# working.net
KiCad netlist of a schematic drawn in EAGLE
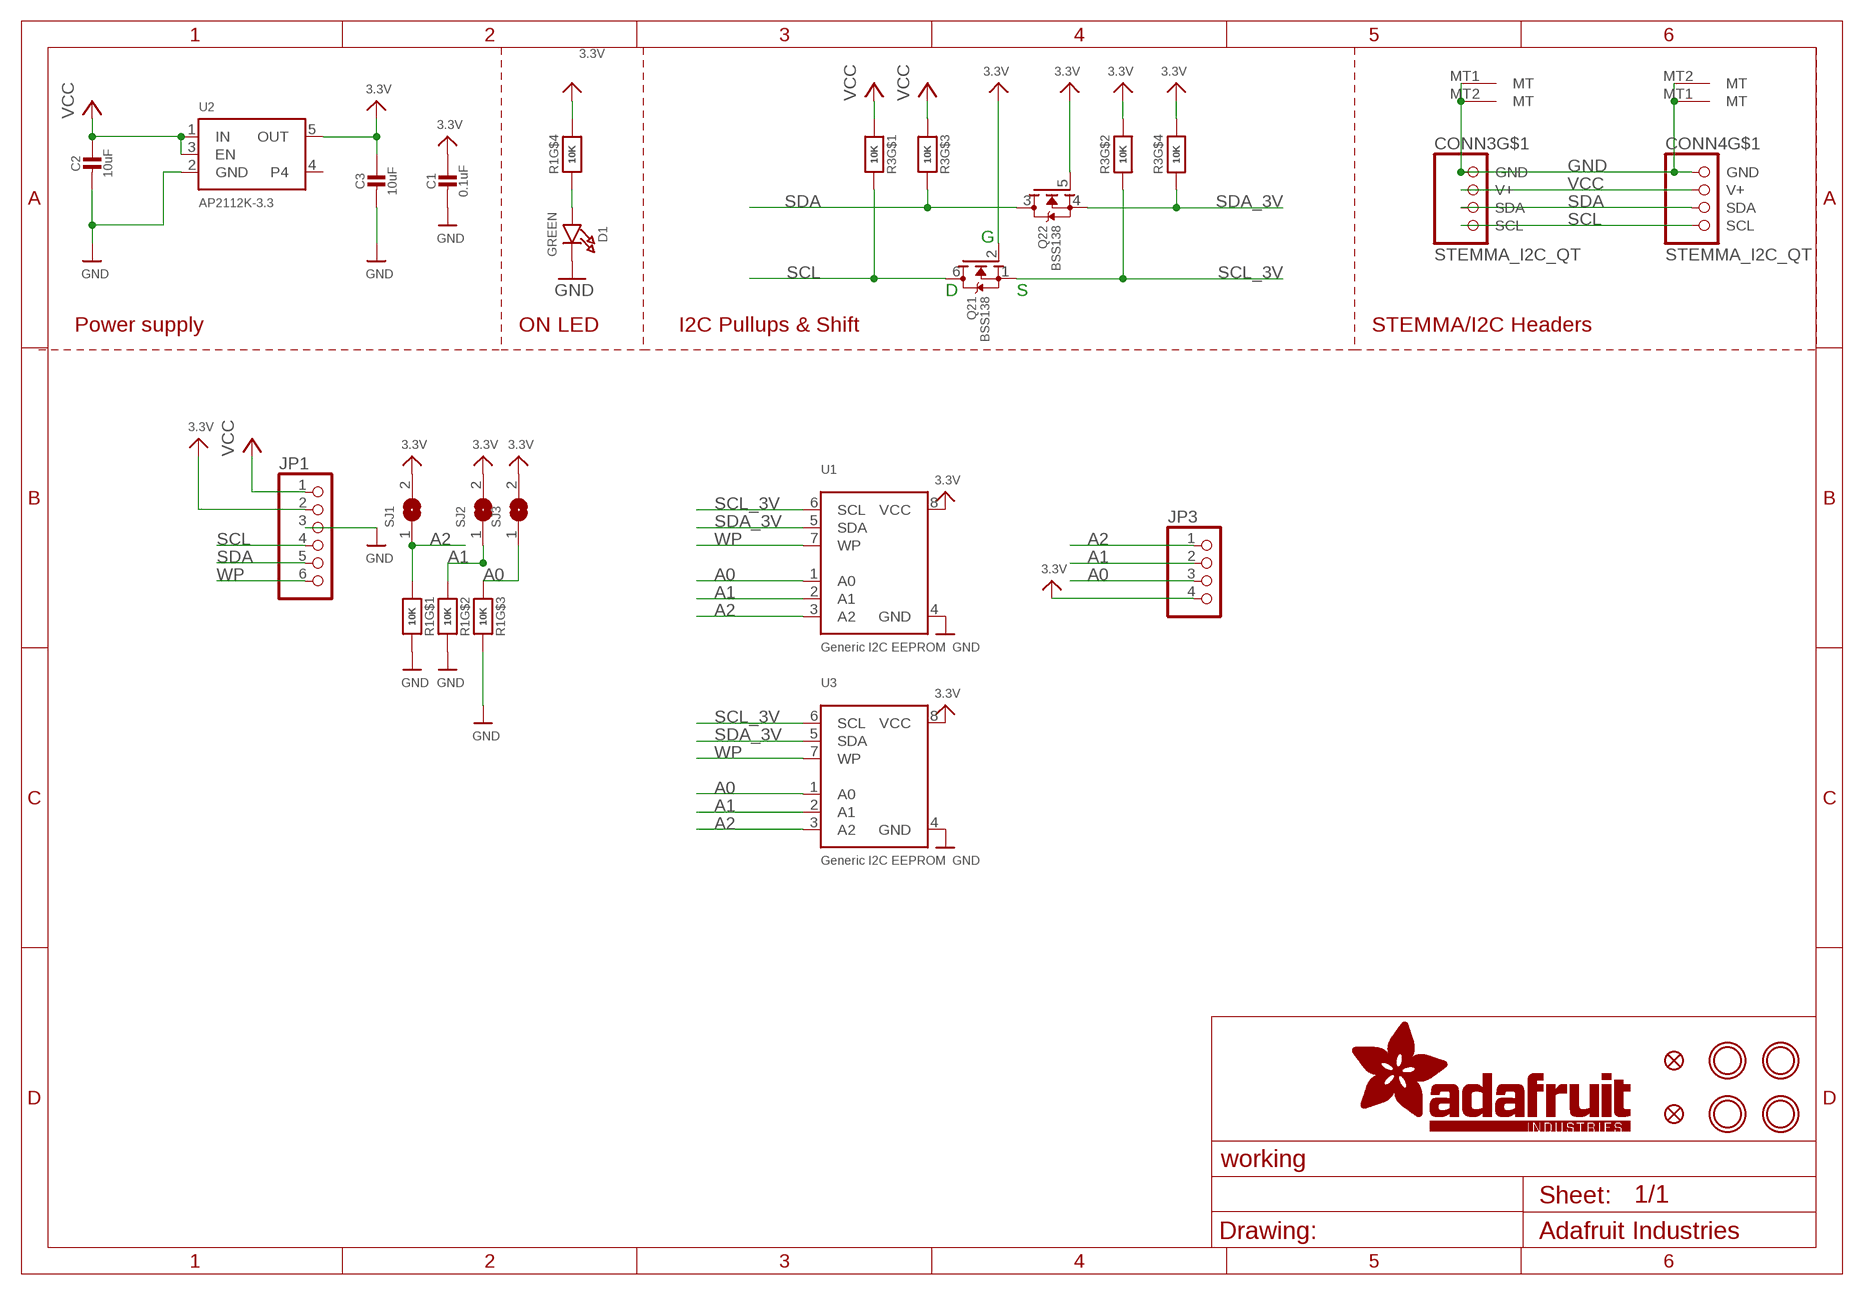
[diagram p0: schematic, sheet 1]

(export (version "E")
  (design (tool "Eeschema 10.0.6"))
  (components
    (comp (ref "C1")
      (value "0.1uF")
      (footprint "eagle-import:0603-NO")
      (libsource (lib "eagle-import") (part "CAP_CERAMIC0603_NO"))
    )
    (comp (ref "C2")
      (value "10uF")
      (footprint "eagle-import:0805-NO")
      (libsource (lib "eagle-import") (part "CAP_CERAMIC0805-NOOUTLINE"))
    )
    (comp (ref "C3")
      (value "10uF")
      (footprint "eagle-import:0805-NO")
      (libsource (lib "eagle-import") (part "CAP_CERAMIC0805-NOOUTLINE"))
    )
    (comp (ref "CONN3")
      (value "STEMMA_I2C_QT")
      (footprint "eagle-import:JST_SH4")
      (libsource (lib "eagle-import") (part "STEMMA_I2C_QT"))
    )
    (comp (ref "CONN4")
      (value "STEMMA_I2C_QT")
      (footprint "eagle-import:JST_SH4")
      (libsource (lib "eagle-import") (part "STEMMA_I2C_QT"))
    )
    (comp (ref "D1")
      (value "GREEN")
      (footprint "eagle-import:CHIPLED_0603_NOOUTLINE")
      (libsource (lib "eagle-import") (part "LED0603_NOOUTLINE"))
    )
    (comp (ref "FID3")
      (value "FIDUCIAL_1MM")
      (footprint "eagle-import:FIDUCIAL_1MM")
      (libsource (lib "eagle-import") (part "FIDUCIAL_1MM"))
    )
    (comp (ref "FID4")
      (value "FIDUCIAL_1MM")
      (footprint "eagle-import:FIDUCIAL_1MM")
      (libsource (lib "eagle-import") (part "FIDUCIAL_1MM"))
    )
    (comp (ref "JP1")
      (value "HEADER-1X670MIL")
      (footprint "eagle-import:1X06_ROUND_70")
      (libsource (lib "eagle-import") (part "HEADER-1X670MIL"))
    )
    (comp (ref "JP3")
      (value "HEADER-1X4ROUND")
      (footprint "eagle-import:1X04_ROUND")
      (libsource (lib "eagle-import") (part "HEADER-1X4ROUND"))
    )
    (comp (ref "Q2")
      (value "BSS138")
      (footprint "eagle-import:SOT363")
      (libsource (lib "eagle-import") (part "MOSFET-N_DUAL"))
    )
    (comp (ref "R1")
      (value "10K")
      (footprint "eagle-import:RESPACK_4X0603")
      (libsource (lib "eagle-import") (part "RESISTOR_4PACK"))
    )
    (comp (ref "R3")
      (value "10K")
      (footprint "eagle-import:RESPACK_4X0603")
      (libsource (lib "eagle-import") (part "RESISTOR_4PACK"))
    )
    (comp (ref "SJ1")
      (value "SOLDERJUMPER")
      (footprint "eagle-import:SOLDERJUMPER_ARROW_NOPASTE")
      (libsource (lib "eagle-import") (part "SOLDERJUMPER"))
    )
    (comp (ref "SJ2")
      (value "SOLDERJUMPER")
      (footprint "eagle-import:SOLDERJUMPER_ARROW_NOPASTE")
      (libsource (lib "eagle-import") (part "SOLDERJUMPER"))
    )
    (comp (ref "SJ3")
      (value "SOLDERJUMPER")
      (footprint "eagle-import:SOLDERJUMPER_ARROW_NOPASTE")
      (libsource (lib "eagle-import") (part "SOLDERJUMPER"))
    )
    (comp (ref "U$1")
      (value "MOUNTINGHOLE2.5")
      (footprint "eagle-import:MOUNTINGHOLE_2.5_PLATED")
      (libsource (lib "eagle-import") (part "MOUNTINGHOLE2.5"))
    )
    (comp (ref "U$17")
      (value "MOUNTINGHOLE2.5")
      (footprint "eagle-import:MOUNTINGHOLE_2.5_PLATED")
      (libsource (lib "eagle-import") (part "MOUNTINGHOLE2.5"))
    )
    (comp (ref "U$19")
      (value "MOUNTINGHOLE2.5")
      (footprint "eagle-import:MOUNTINGHOLE_2.5_PLATED")
      (libsource (lib "eagle-import") (part "MOUNTINGHOLE2.5"))
    )
    (comp (ref "U$21")
      (value "MOUNTINGHOLE2.5")
      (footprint "eagle-import:MOUNTINGHOLE_2.5_PLATED")
      (libsource (lib "eagle-import") (part "MOUNTINGHOLE2.5"))
    )
    (comp (ref "U1")
      (value "Generic I2C EEPROM")
      (footprint "eagle-import:SOIC8_150MIL")
      (libsource (lib "eagle-import") (part "EEPROM_I2C_8PIN_GENERIC"))
    )
    (comp (ref "U2")
      (value "AP2112K-3.3")
      (footprint "eagle-import:SOT23-5")
      (libsource (lib "eagle-import") (part "VREG_SOT23-5"))
    )
    (comp (ref "U3")
      (value "Generic I2C EEPROM")
      (footprint "eagle-import:USON8")
      (libsource (lib "eagle-import") (part "EEPROM_I2C_8PIN_GENERIC_SON8"))
    )
  )
  (nets
    (net (code "1") (name "/A0") (class "Default")
      (node (ref "JP3") (pin "3") (pinfunction "3_3") (pintype "passive"))
      (node (ref "R1") (pin "3") (pinfunction "1_3") (pintype "passive"))
      (node (ref "SJ3") (pin "1") (pinfunction "1_1") (pintype "passive"))
      (node (ref "U1") (pin "1") (pinfunction "A0_1") (pintype "input"))
      (node (ref "U3") (pin "1") (pinfunction "A0_1") (pintype "input"))
    )
    (net (code "2") (name "/A1") (class "Default")
      (node (ref "JP3") (pin "2") (pinfunction "2_2") (pintype "passive"))
      (node (ref "R1") (pin "2") (pinfunction "1_2") (pintype "passive"))
      (node (ref "SJ2") (pin "1") (pinfunction "1_1") (pintype "passive"))
      (node (ref "U1") (pin "2") (pinfunction "A1_2") (pintype "input"))
      (node (ref "U3") (pin "2") (pinfunction "A1_2") (pintype "input"))
    )
    (net (code "3") (name "/A2") (class "Default")
      (node (ref "JP3") (pin "1") (pinfunction "1_1") (pintype "passive"))
      (node (ref "R1") (pin "1") (pinfunction "1_1") (pintype "passive"))
      (node (ref "SJ1") (pin "1") (pinfunction "1_1") (pintype "passive"))
      (node (ref "U1") (pin "3") (pinfunction "A2_3") (pintype "input"))
      (node (ref "U3") (pin "3") (pinfunction "A2_3") (pintype "input"))
    )
    (net (code "4") (name "/SCL") (class "Default")
      (node (ref "CONN3") (pin "4") (pinfunction "SCL_4") (pintype "passive"))
      (node (ref "CONN4") (pin "4") (pinfunction "SCL_4") (pintype "passive"))
      (node (ref "JP1") (pin "4") (pinfunction "4_4") (pintype "passive"))
      (node (ref "Q2") (pin "6") (pinfunction "D_6") (pintype "bidirectional"))
      (node (ref "R3") (pin "8") (pinfunction "2_8") (pintype "passive"))
    )
    (net (code "5") (name "/SCL_3V") (class "Default")
      (node (ref "Q2") (pin "1") (pinfunction "S_1") (pintype "bidirectional"))
      (node (ref "R3") (pin "7") (pinfunction "2_7") (pintype "passive"))
      (node (ref "U1") (pin "6") (pinfunction "SCL_6") (pintype "input"))
      (node (ref "U3") (pin "6") (pinfunction "SCL_6") (pintype "input"))
    )
    (net (code "6") (name "/SDA") (class "Default")
      (node (ref "CONN3") (pin "3") (pinfunction "SDA_3") (pintype "passive"))
      (node (ref "CONN4") (pin "3") (pinfunction "SDA_3") (pintype "passive"))
      (node (ref "JP1") (pin "5") (pinfunction "5_5") (pintype "passive"))
      (node (ref "Q2") (pin "3") (pinfunction "D_3") (pintype "bidirectional"))
      (node (ref "R3") (pin "6") (pinfunction "2_6") (pintype "passive"))
    )
    (net (code "7") (name "/SDA_3V") (class "Default")
      (node (ref "Q2") (pin "4") (pinfunction "S_4") (pintype "bidirectional"))
      (node (ref "R3") (pin "5") (pinfunction "2_5") (pintype "passive"))
      (node (ref "U1") (pin "5") (pinfunction "SDA_5") (pintype "bidirectional"))
      (node (ref "U3") (pin "5") (pinfunction "SDA_5") (pintype "bidirectional"))
    )
    (net (code "8") (name "/WP") (class "Default")
      (node (ref "JP1") (pin "6") (pinfunction "6_6") (pintype "passive"))
      (node (ref "U1") (pin "7") (pinfunction "WP_7") (pintype "input"))
      (node (ref "U3") (pin "7") (pinfunction "WP_7") (pintype "input"))
    )
    (net (code "9") (name "3.3V") (class "Default")
      (node (ref "C1") (pin "1") (pinfunction "1_1") (pintype "passive"))
      (node (ref "C3") (pin "1") (pinfunction "1_1") (pintype "passive"))
      (node (ref "JP1") (pin "2") (pinfunction "2_2") (pintype "passive"))
      (node (ref "JP3") (pin "4") (pinfunction "4_4") (pintype "passive"))
      (node (ref "Q2") (pin "2") (pinfunction "G_2") (pintype "bidirectional"))
      (node (ref "Q2") (pin "5") (pinfunction "G_5") (pintype "bidirectional"))
      (node (ref "R1") (pin "5") (pinfunction "2_5") (pintype "passive"))
      (node (ref "R3") (pin "2") (pinfunction "1_2") (pintype "passive"))
      (node (ref "R3") (pin "4") (pinfunction "1_4") (pintype "passive"))
      (node (ref "SJ1") (pin "2") (pinfunction "2_2") (pintype "passive"))
      (node (ref "SJ2") (pin "2") (pinfunction "2_2") (pintype "passive"))
      (node (ref "SJ3") (pin "2") (pinfunction "2_2") (pintype "passive"))
      (node (ref "U1") (pin "8") (pinfunction "VCC_8") (pintype "power_in"))
      (node (ref "U2") (pin "5") (pinfunction "OUT_5") (pintype "power_in"))
      (node (ref "U3") (pin "8") (pinfunction "VCC_8") (pintype "power_in"))
    )
    (net (code "10") (name "GND") (class "Default")
      (node (ref "C1") (pin "2") (pinfunction "2_2") (pintype "passive"))
      (node (ref "C2") (pin "2") (pinfunction "2_2") (pintype "passive"))
      (node (ref "C3") (pin "2") (pinfunction "2_2") (pintype "passive"))
      (node (ref "CONN3") (pin "1") (pinfunction "GND_1") (pintype "passive"))
      (node (ref "CONN3") (pin "MT1") (pinfunction "MT_MT1") (pintype "bidirectional"))
      (node (ref "CONN3") (pin "MT2") (pinfunction "MT_MT2") (pintype "bidirectional"))
      (node (ref "CONN4") (pin "1") (pinfunction "GND_1") (pintype "passive"))
      (node (ref "CONN4") (pin "MT1") (pinfunction "MT_MT1") (pintype "bidirectional"))
      (node (ref "CONN4") (pin "MT2") (pinfunction "MT_MT2") (pintype "bidirectional"))
      (node (ref "D1") (pin "C") (pinfunction "C_C") (pintype "passive"))
      (node (ref "JP1") (pin "3") (pinfunction "3_3") (pintype "passive"))
      (node (ref "R1") (pin "6") (pinfunction "2_6") (pintype "passive"))
      (node (ref "R1") (pin "7") (pinfunction "2_7") (pintype "passive"))
      (node (ref "R1") (pin "8") (pinfunction "2_8") (pintype "passive"))
      (node (ref "U1") (pin "4") (pinfunction "GND_4") (pintype "power_in"))
      (node (ref "U2") (pin "2") (pinfunction "GND_2") (pintype "power_in"))
      (node (ref "U3") (pin "4") (pinfunction "GND_4") (pintype "power_in"))
    )
    (net (code "11") (name "Net-(R1D-1)") (class "Default")
      (node (ref "D1") (pin "A") (pinfunction "A_A") (pintype "passive"))
      (node (ref "R1") (pin "4") (pinfunction "1_4") (pintype "passive"))
    )
    (net (code "12") (name "VCC") (class "Default")
      (node (ref "C2") (pin "1") (pinfunction "1_1") (pintype "passive"))
      (node (ref "CONN3") (pin "2") (pinfunction "V+_2") (pintype "passive"))
      (node (ref "CONN4") (pin "2") (pinfunction "V+_2") (pintype "passive"))
      (node (ref "JP1") (pin "1") (pinfunction "1_1") (pintype "passive"))
      (node (ref "R3") (pin "1") (pinfunction "1_1") (pintype "passive"))
      (node (ref "R3") (pin "3") (pinfunction "1_3") (pintype "passive"))
      (node (ref "U2") (pin "1") (pinfunction "IN_1") (pintype "power_in"))
      (node (ref "U2") (pin "3") (pinfunction "EN_3") (pintype "input"))
    )
    (net (code "13") (name "unconnected-(U2-P4-Pad4)") (class "Default")
      (node (ref "U2") (pin "4") (pinfunction "P4_4") (pintype "bidirectional"))
    )
  )
)
